# Fri3D_2024_Power.net
KiCad netlist of a schematic drawn in Altium Designer
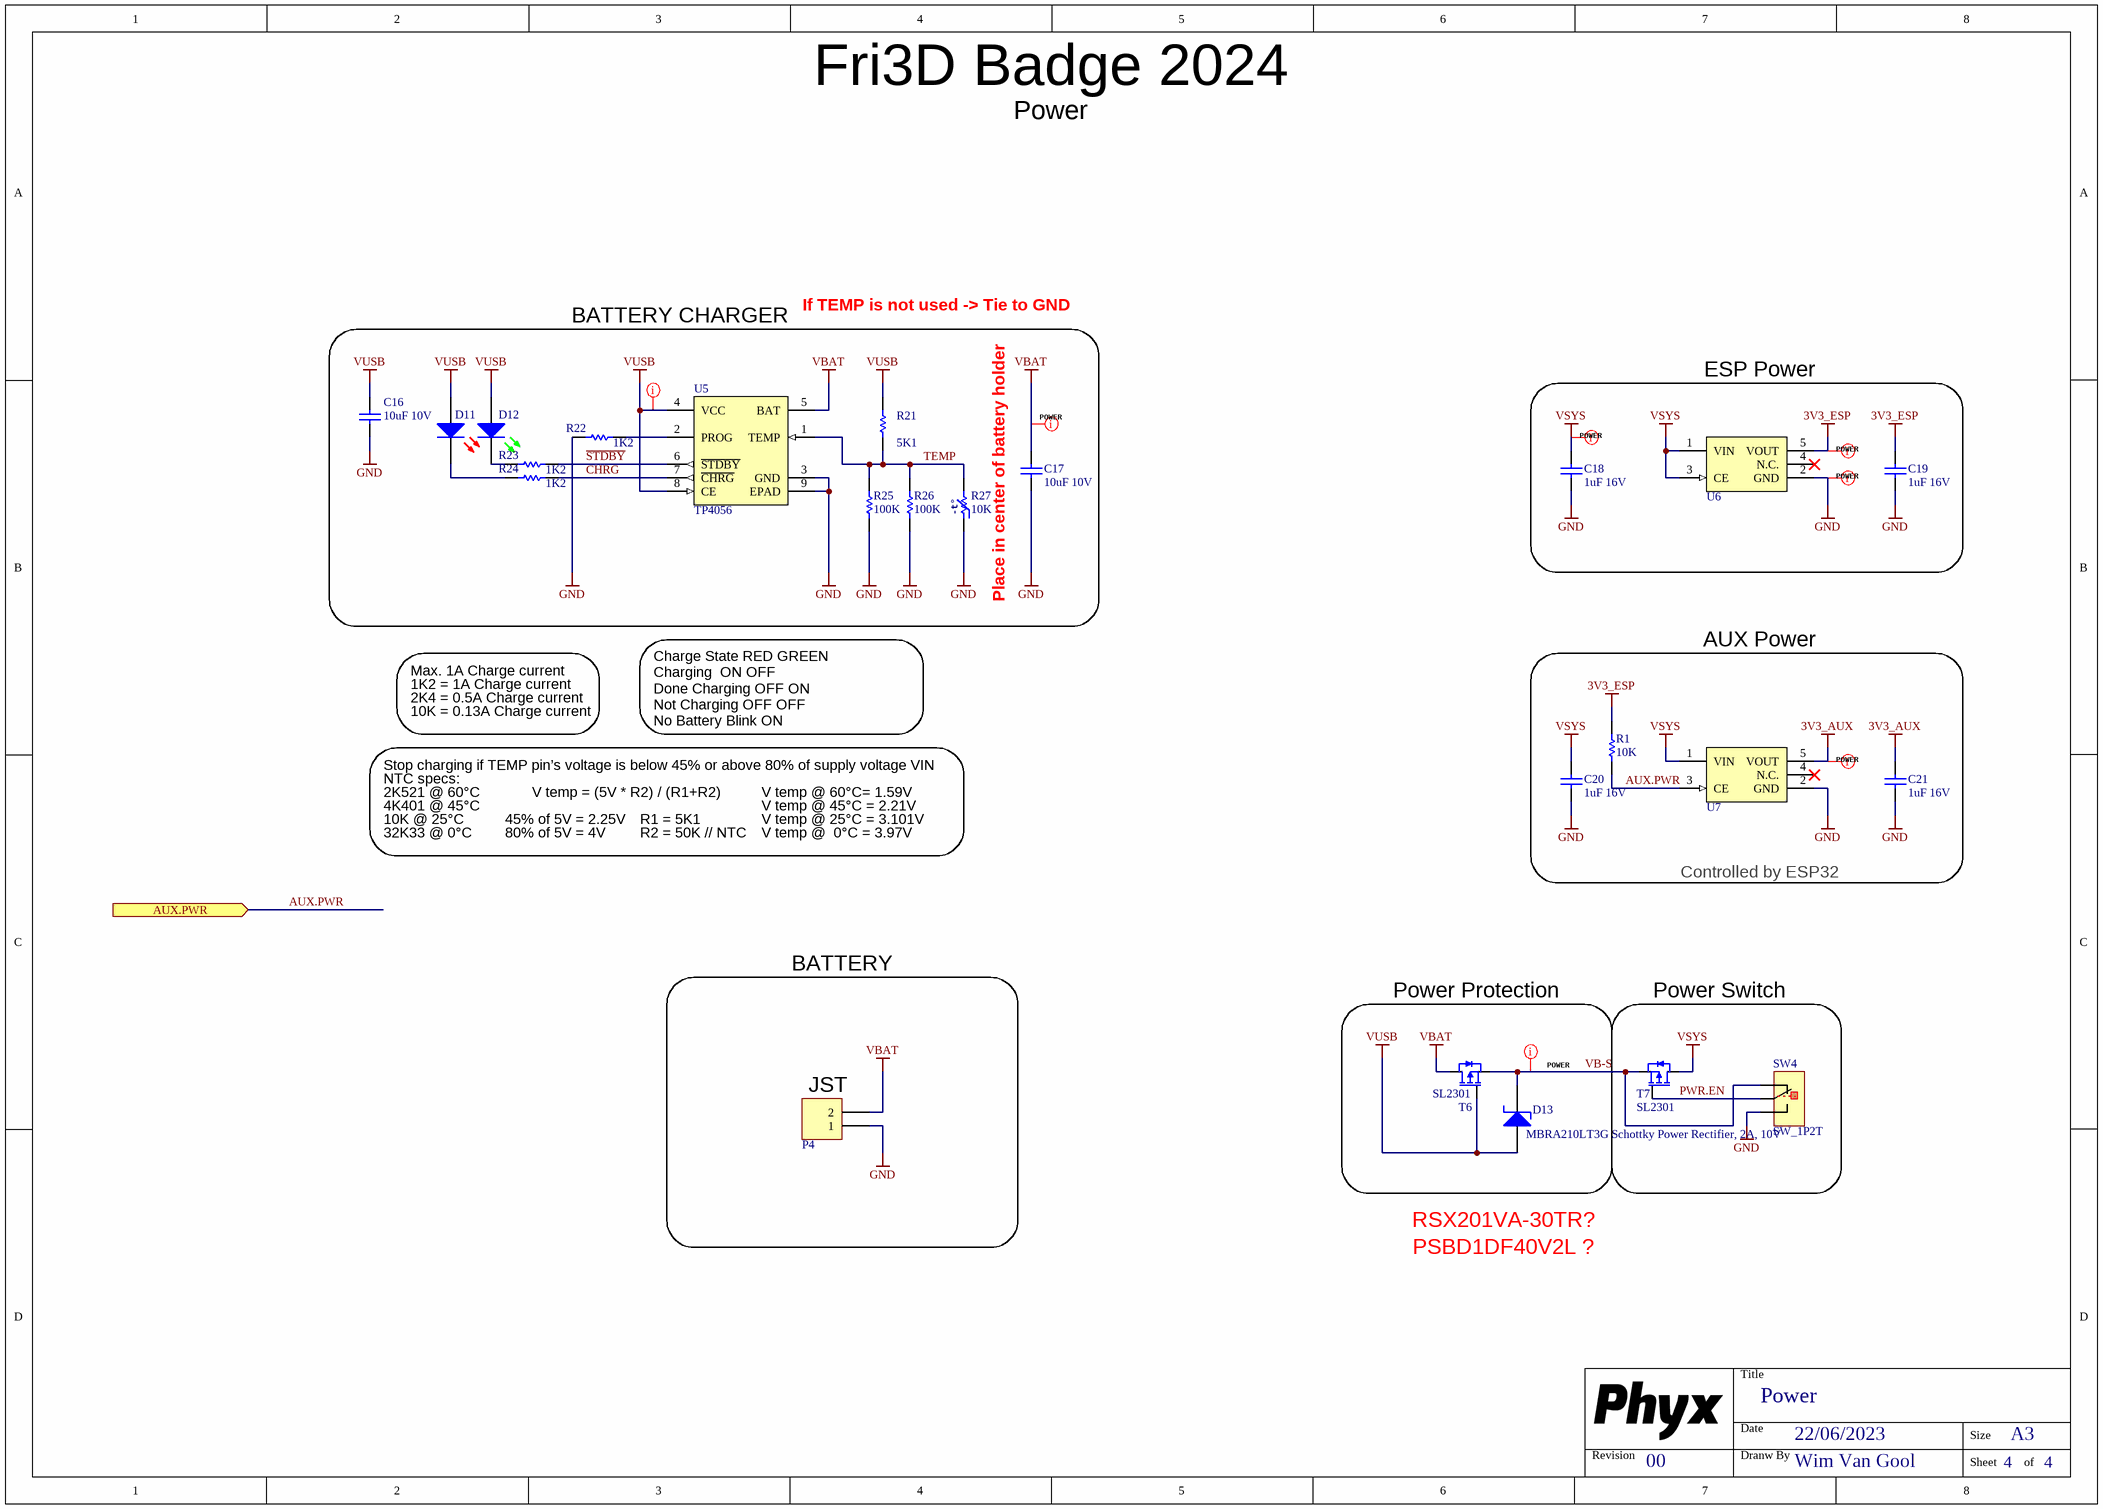
[diagram p0: Fri3D_2024_Power.SchDoc]

(export (version "E")
  (design (tool "Eeschema 10.0.6"))
  (components
    (comp (ref "C16")
      (value "10uF 10V")
      (footprint "C0805_N")
      (description "Capacitor Ceramic")
      (fields (field (name "Comment") "CAP_CERAMIC"))
      (libsource (lib "Phyx_Components") (part "CAP_CERAMIC"))
    )
    (comp (ref "C17")
      (value "10uF 10V")
      (footprint "C0805_N")
      (description "Capacitor Ceramic")
      (fields (field (name "Comment") "CAP_CERAMIC"))
      (libsource (lib "Phyx_Components") (part "CAP_CERAMIC"))
    )
    (comp (ref "C18")
      (value "1uF 16V")
      (footprint "C0603_N")
      (description "Capacitor Ceramic")
      (fields (field (name "Comment") "CAP_CERAMIC"))
      (libsource (lib "Phyx_Components") (part "CAP_CERAMIC"))
    )
    (comp (ref "C19")
      (value "1uF 16V")
      (footprint "C0603_N")
      (description "Capacitor Ceramic")
      (fields (field (name "Comment") "CAP_CERAMIC"))
      (libsource (lib "Phyx_Components") (part "CAP_CERAMIC"))
    )
    (comp (ref "C20")
      (value "1uF 16V")
      (footprint "C0603_N")
      (description "Capacitor Ceramic")
      (fields (field (name "Comment") "CAP_CERAMIC"))
      (libsource (lib "Phyx_Components") (part "CAP_CERAMIC"))
    )
    (comp (ref "C21")
      (value "1uF 16V")
      (footprint "C0603_N")
      (description "Capacitor Ceramic")
      (fields (field (name "Comment") "CAP_CERAMIC"))
      (libsource (lib "Phyx_Components") (part "CAP_CERAMIC"))
    )
    (comp (ref "D11")
      (value "Default 0805 Red LED")
      (footprint "LED_0805_RD")
      (description "=Description")
      (libsource (lib "Phyx_Components") (part "LED_RED"))
    )
    (comp (ref "D12")
      (value "Default 0805 Green LED")
      (footprint "LED_0805_GR")
      (description "=Description")
      (libsource (lib "Phyx_Components") (part "LED_GREEN"))
    )
    (comp (ref "D13")
      (value "MBRA210LT3G Schottky Power Rectifier, 2A, 10V")
      (footprint "SMA_AC")
      (description "=Description")
      (libsource (lib "Phyx_Components") (part "Schottky_AC"))
    )
    (comp (ref "P4")
      (value "Header RA 1.5mm Shrouded S2B-ZR-SM4A-TF")
      (footprint "JST_ZH_S2B-ZR-SM4A-TF")
      (libsource (lib "Phyx_Components") (part "Header 2"))
    )
    (comp (ref "R1")
      (value "10K")
      (footprint "R0603_N")
      (fields (field (name "Comment") "RESISTOR"))
      (libsource (lib "Phyx_Components") (part "RESISTOR"))
    )
    (comp (ref "R21")
      (value "5K1")
      (footprint "R0603_N")
      (fields (field (name "Comment") "RESISTOR"))
      (libsource (lib "Phyx_Components") (part "RESISTOR"))
    )
    (comp (ref "R22")
      (value "1K2")
      (footprint "R0603_N")
      (fields (field (name "Comment") "RESISTOR"))
      (libsource (lib "Phyx_Components") (part "RESISTOR"))
    )
    (comp (ref "R23")
      (value "1K2")
      (footprint "R0603_N")
      (fields (field (name "Comment") "RESISTOR"))
      (libsource (lib "Phyx_Components") (part "RESISTOR"))
    )
    (comp (ref "R24")
      (value "1K2")
      (footprint "R0603_N")
      (fields (field (name "Comment") "RESISTOR"))
      (libsource (lib "Phyx_Components") (part "RESISTOR"))
    )
    (comp (ref "R25")
      (value "100K")
      (footprint "R0603_N")
      (fields (field (name "Comment") "RESISTOR"))
      (libsource (lib "Phyx_Components") (part "RESISTOR"))
    )
    (comp (ref "R26")
      (value "100K")
      (footprint "R0603_N")
      (fields (field (name "Comment") "RESISTOR"))
      (libsource (lib "Phyx_Components") (part "RESISTOR"))
    )
    (comp (ref "R27")
      (value "10K")
      (footprint "R0402")
      (fields (field (name "Comment") "NTC"))
      (libsource (lib "Phyx_Components") (part "RESISTOR_NTC"))
    )
    (comp (ref "SW4")
      (value "SW_1P2T")
      (footprint "WE_450404015514")
      (libsource (lib "Phyx_Components") (part "SW_1P2T"))
    )
    (comp (ref "T6")
      (value "SL2301")
      (footprint "SOT23-3")
      (description "=Description")
      (fields (field (name "Comment") "-2.3A -20V P-Ch MOSFET Vgs -1V"))
      (libsource (lib "Phyx_Components") (part "P_MOSFET_GSD"))
    )
    (comp (ref "T7")
      (value "SL2301")
      (footprint "SOT23-3")
      (description "=Description")
      (fields (field (name "Comment") "-2.3A -20V P-Ch MOSFET Vgs -1V"))
      (libsource (lib "Phyx_Components") (part "P_MOSFET_GSD"))
    )
    (comp (ref "U5")
      (value "TP4056")
      (footprint "SOIC_N_8_TH")
      (description "=Description")
      (fields (field (name "Comment") "Single Cell LiIon charger max 1A"))
      (libsource (lib "Phyx_Components") (part "TP4056"))
    )
    (comp (ref "U6")
      (value "3V3 LDO 700mA 50mV")
      (footprint "SOT23-5")
      (description "=Designator")
      (libsource (lib "Phyx_Components") (part "XC6210_SOT"))
    )
    (comp (ref "U7")
      (value "3V3 LDO 700mA 50mV")
      (footprint "SOT23-5")
      (description "=Designator")
      (libsource (lib "Phyx_Components") (part "XC6210_SOT"))
    )
  )
  (nets
    (net (code "1") (name "/AUX.PWR") (class "Default")
      (node (ref "R1") (pin "2") (pinfunction "2_2") (pintype "passive"))
      (node (ref "U7") (pin "3") (pinfunction "CE_3") (pintype "input"))
    )
    (net (code "2") (name "/PWR.EN") (class "Default")
      (node (ref "SW4") (pin "2") (pinfunction "2_2") (pintype "passive"))
      (node (ref "T7") (pin "1") (pinfunction "G_1") (pintype "passive"))
    )
    (net (code "3") (name "/TEMP") (class "Default")
      (node (ref "R21") (pin "2") (pinfunction "2_2") (pintype "passive"))
      (node (ref "R25") (pin "1") (pinfunction "1_1") (pintype "passive"))
      (node (ref "R26") (pin "1") (pinfunction "1_1") (pintype "passive"))
      (node (ref "R27") (pin "1") (pinfunction "1_1") (pintype "passive"))
      (node (ref "U5") (pin "1") (pinfunction "TEMP_1") (pintype "input"))
    )
    (net (code "4") (name "/VB-S") (class "Default")
      (node (ref "D13") (pin "C") (pinfunction "C_C") (pintype "passive"))
      (node (ref "SW4") (pin "1") (pinfunction "1_1") (pintype "passive"))
      (node (ref "T6") (pin "2") (pinfunction "S_2") (pintype "passive"))
      (node (ref "T7") (pin "2") (pinfunction "S_2") (pintype "passive"))
    )
    (net (code "5") (name "/~{CHRG}") (class "Default")
      (node (ref "R24") (pin "2") (pinfunction "2_2") (pintype "passive"))
      (node (ref "U5") (pin "7") (pinfunction "~{CHRG}_7") (pintype "output"))
    )
    (net (code "6") (name "/~{STDBY}") (class "Default")
      (node (ref "R23") (pin "2") (pinfunction "2_2") (pintype "passive"))
      (node (ref "U5") (pin "6") (pinfunction "~{STDBY}_6") (pintype "output"))
    )
    (net (code "7") (name "3V3_AUX") (class "Default")
      (node (ref "C21") (pin "1") (pinfunction "1_1") (pintype "passive"))
      (node (ref "U7") (pin "5") (pinfunction "VOUT_5") (pintype "power_in"))
    )
    (net (code "8") (name "3V3_ESP") (class "Default")
      (node (ref "C19") (pin "1") (pinfunction "1_1") (pintype "passive"))
      (node (ref "R1") (pin "1") (pinfunction "1_1") (pintype "passive"))
      (node (ref "U6") (pin "5") (pinfunction "VOUT_5") (pintype "power_in"))
    )
    (net (code "9") (name "GND") (class "Default")
      (node (ref "C16") (pin "2") (pinfunction "2_2") (pintype "passive"))
      (node (ref "C17") (pin "2") (pinfunction "2_2") (pintype "passive"))
      (node (ref "C18") (pin "2") (pinfunction "2_2") (pintype "passive"))
      (node (ref "C19") (pin "2") (pinfunction "2_2") (pintype "passive"))
      (node (ref "C20") (pin "2") (pinfunction "2_2") (pintype "passive"))
      (node (ref "C21") (pin "2") (pinfunction "2_2") (pintype "passive"))
      (node (ref "P4") (pin "1") (pinfunction "1_1") (pintype "passive"))
      (node (ref "R22") (pin "2") (pinfunction "2_2") (pintype "passive"))
      (node (ref "R25") (pin "2") (pinfunction "2_2") (pintype "passive"))
      (node (ref "R26") (pin "2") (pinfunction "2_2") (pintype "passive"))
      (node (ref "R27") (pin "2") (pinfunction "2_2") (pintype "passive"))
      (node (ref "SW4") (pin "3") (pinfunction "3_3") (pintype "passive"))
      (node (ref "U5") (pin "3") (pinfunction "GND_3") (pintype "power_in"))
      (node (ref "U5") (pin "9") (pinfunction "EPAD_9") (pintype "power_in"))
      (node (ref "U6") (pin "2") (pinfunction "GND_2") (pintype "power_in"))
      (node (ref "U7") (pin "2") (pinfunction "GND_2") (pintype "power_in"))
    )
    (net (code "10") (name "Net-(D11-K)") (class "Default")
      (node (ref "D11") (pin "2") (pinfunction "K_2") (pintype "passive"))
      (node (ref "R24") (pin "1") (pinfunction "1_1") (pintype "passive"))
    )
    (net (code "11") (name "Net-(D12-K)") (class "Default")
      (node (ref "D12") (pin "2") (pinfunction "K_2") (pintype "passive"))
      (node (ref "R23") (pin "1") (pinfunction "1_1") (pintype "passive"))
    )
    (net (code "12") (name "Net-(U5-PROG)") (class "Default")
      (node (ref "R22") (pin "1") (pinfunction "1_1") (pintype "passive"))
      (node (ref "U5") (pin "2") (pinfunction "PROG_2") (pintype "passive"))
    )
    (net (code "13") (name "VBAT") (class "Default")
      (node (ref "C17") (pin "1") (pinfunction "1_1") (pintype "passive"))
      (node (ref "P4") (pin "2") (pinfunction "2_2") (pintype "passive"))
      (node (ref "T6") (pin "3") (pinfunction "D_3") (pintype "passive"))
      (node (ref "U5") (pin "5") (pinfunction "BAT_5") (pintype "power_in"))
    )
    (net (code "14") (name "VSYS") (class "Default")
      (node (ref "C18") (pin "1") (pinfunction "1_1") (pintype "passive"))
      (node (ref "C20") (pin "1") (pinfunction "1_1") (pintype "passive"))
      (node (ref "T7") (pin "3") (pinfunction "D_3") (pintype "passive"))
      (node (ref "U6") (pin "1") (pinfunction "VIN_1") (pintype "power_in"))
      (node (ref "U6") (pin "3") (pinfunction "CE_3") (pintype "input"))
      (node (ref "U7") (pin "1") (pinfunction "VIN_1") (pintype "power_in"))
    )
    (net (code "15") (name "VUSB") (class "Default")
      (node (ref "C16") (pin "1") (pinfunction "1_1") (pintype "passive"))
      (node (ref "D11") (pin "1") (pinfunction "A_1") (pintype "passive"))
      (node (ref "D12") (pin "1") (pinfunction "A_1") (pintype "passive"))
      (node (ref "D13") (pin "A") (pinfunction "A_A") (pintype "passive"))
      (node (ref "R21") (pin "1") (pinfunction "1_1") (pintype "passive"))
      (node (ref "T6") (pin "1") (pinfunction "G_1") (pintype "passive"))
      (node (ref "U5") (pin "4") (pinfunction "VCC_4") (pintype "power_in"))
      (node (ref "U5") (pin "8") (pinfunction "CE_8") (pintype "input"))
    )
    (net (code "16") (name "unconnected-(U6-N.C.-Pad4)") (class "Default")
      (node (ref "U6") (pin "4") (pinfunction "N.C._4") (pintype "passive+no_connect"))
    )
    (net (code "17") (name "unconnected-(U7-N.C.-Pad4)") (class "Default")
      (node (ref "U7") (pin "4") (pinfunction "N.C._4") (pintype "passive+no_connect"))
    )
  )
)
